# LB-w3-DOUBLE_OR_v02_rev2.net
KiCad netlist of a schematic drawn in EAGLE
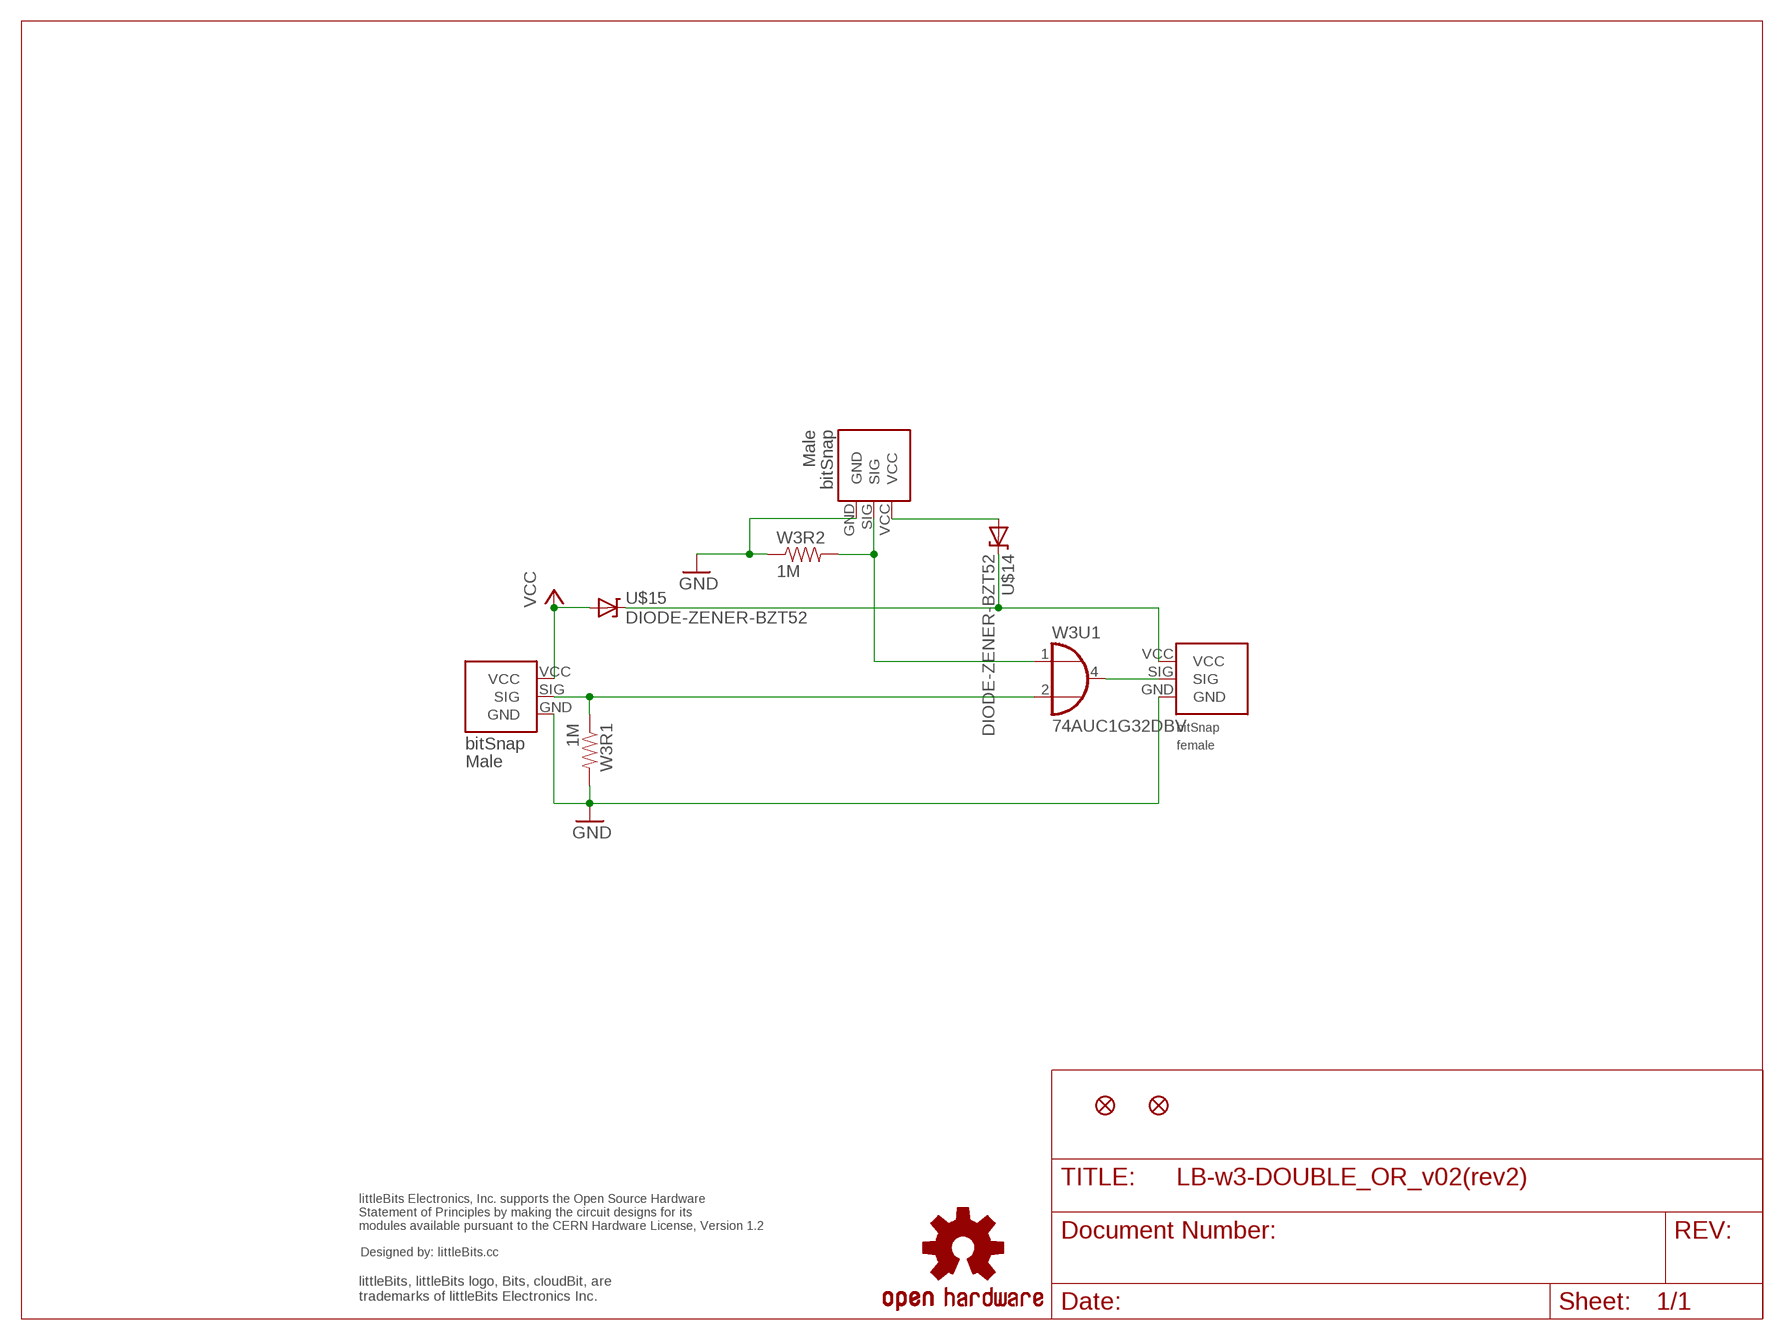
[diagram p0: schematic, sheet 1]

(export (version "E")
  (design (tool "Eeschema 10.0.6"))
  (components
    (comp (ref "U$1")
      (value "OSHWCREDIT")
      (footprint "eagle-import:OSHWCREDIT")
      (libsource (lib "eagle-import") (part "OSHWCREDIT"))
    )
    (comp (ref "U$2")
      (value "OSHW-LOGOL")
      (footprint "eagle-import:OSHW-LOGO-L")
      (libsource (lib "eagle-import") (part "OSHW-LOGOL"))
    )
    (comp (ref "U$14")
      (value "DIODE-ZENER-BZT52")
      (footprint "eagle-import:SOD-323")
      (libsource (lib "eagle-import") (part "DIODE-ZENER-BZT52"))
    )
    (comp (ref "U$15")
      (value "DIODE-ZENER-BZT52")
      (footprint "eagle-import:SOD-323")
      (libsource (lib "eagle-import") (part "DIODE-ZENER-BZT52"))
    )
    (comp (ref "W3BSF")
      (value "BITSNAP_FEMALE")
      (footprint "eagle-import:BITSNAP_FEMALE")
      (libsource (lib "eagle-import") (part "BITSNAP_FEMALE"))
    )
    (comp (ref "W3BSM")
      (value "BITSNAP_MALE")
      (footprint "eagle-import:BITSNAP_MALE")
      (libsource (lib "eagle-import") (part "BITSNAP_MALE"))
    )
    (comp (ref "W3BSM1")
      (value "BITSNAP_MALE")
      (footprint "eagle-import:BITSNAP_MALE")
      (libsource (lib "eagle-import") (part "BITSNAP_MALE"))
    )
    (comp (ref "W3FD1")
      (value "FIDUCIAL1X2")
      (footprint "eagle-import:FIDUCIAL-1X2")
      (libsource (lib "eagle-import") (part "FIDUCIAL1X2"))
    )
    (comp (ref "W3FD2")
      (value "FIDUCIAL1X2")
      (footprint "eagle-import:FIDUCIAL-1X2")
      (libsource (lib "eagle-import") (part "FIDUCIAL1X2"))
    )
    (comp (ref "W3R1")
      (value "1M")
      (footprint "eagle-import:0603-RES")
      (libsource (lib "eagle-import") (part "RESISTOR0603-RES"))
    )
    (comp (ref "W3R2")
      (value "1M")
      (footprint "eagle-import:0603-RES")
      (libsource (lib "eagle-import") (part "RESISTOR0603-RES"))
    )
    (comp (ref "W3U1")
      (value "74AUC1G32DBV")
      (footprint "eagle-import:SOT23-5")
      (libsource (lib "eagle-import") (part "741G32DBVAUC"))
    )
  )
  (nets
    (net (code "1") (name "GND") (class "Default")
      (node (ref "W3BSF") (pin "GND") (pinfunction "GND_GND") (pintype "bidirectional"))
      (node (ref "W3BSM") (pin "GND") (pinfunction "GND_GND") (pintype "bidirectional"))
      (node (ref "W3BSM1") (pin "GND") (pinfunction "GND_GND") (pintype "bidirectional"))
      (node (ref "W3R1") (pin "2") (pinfunction "2_2") (pintype "passive"))
      (node (ref "W3R2") (pin "1") (pinfunction "1_1") (pintype "passive"))
    )
    (net (code "2") (name "Net-(U$14-A)") (class "Default")
      (node (ref "U$14") (pin "2") (pinfunction "A_2") (pintype "passive"))
      (node (ref "W3BSM") (pin "VCC") (pinfunction "VCC_VCC") (pintype "bidirectional"))
    )
    (net (code "3") (name "Net-(U$14-C)") (class "Default")
      (node (ref "U$14") (pin "1") (pinfunction "C_1") (pintype "passive"))
      (node (ref "U$15") (pin "1") (pinfunction "C_1") (pintype "passive"))
      (node (ref "W3BSF") (pin "VCC") (pinfunction "VCC_VCC") (pintype "bidirectional"))
    )
    (net (code "4") (name "Net-(W3U1A-I0)") (class "Default")
      (node (ref "W3BSM") (pin "SIG") (pinfunction "SIG_SIG") (pintype "bidirectional"))
      (node (ref "W3R2") (pin "2") (pinfunction "2_2") (pintype "passive"))
      (node (ref "W3U1") (pin "1") (pinfunction "I0_1") (pintype "input"))
    )
    (net (code "5") (name "Net-(W3U1A-I1)") (class "Default")
      (node (ref "W3BSM1") (pin "SIG") (pinfunction "SIG_SIG") (pintype "bidirectional"))
      (node (ref "W3R1") (pin "1") (pinfunction "1_1") (pintype "passive"))
      (node (ref "W3U1") (pin "2") (pinfunction "I1_2") (pintype "input"))
    )
    (net (code "6") (name "Net-(W3U1A-O)") (class "Default")
      (node (ref "W3BSF") (pin "SIG") (pinfunction "SIG_SIG") (pintype "bidirectional"))
      (node (ref "W3U1") (pin "4") (pinfunction "O_4") (pintype "output"))
    )
    (net (code "7") (name "VCC") (class "Default")
      (node (ref "U$15") (pin "2") (pinfunction "A_2") (pintype "passive"))
      (node (ref "W3BSM1") (pin "VCC") (pinfunction "VCC_VCC") (pintype "bidirectional"))
    )
  )
)
